# BPM_Mainboard.net
KiCad netlist of a schematic drawn in Altium Designer
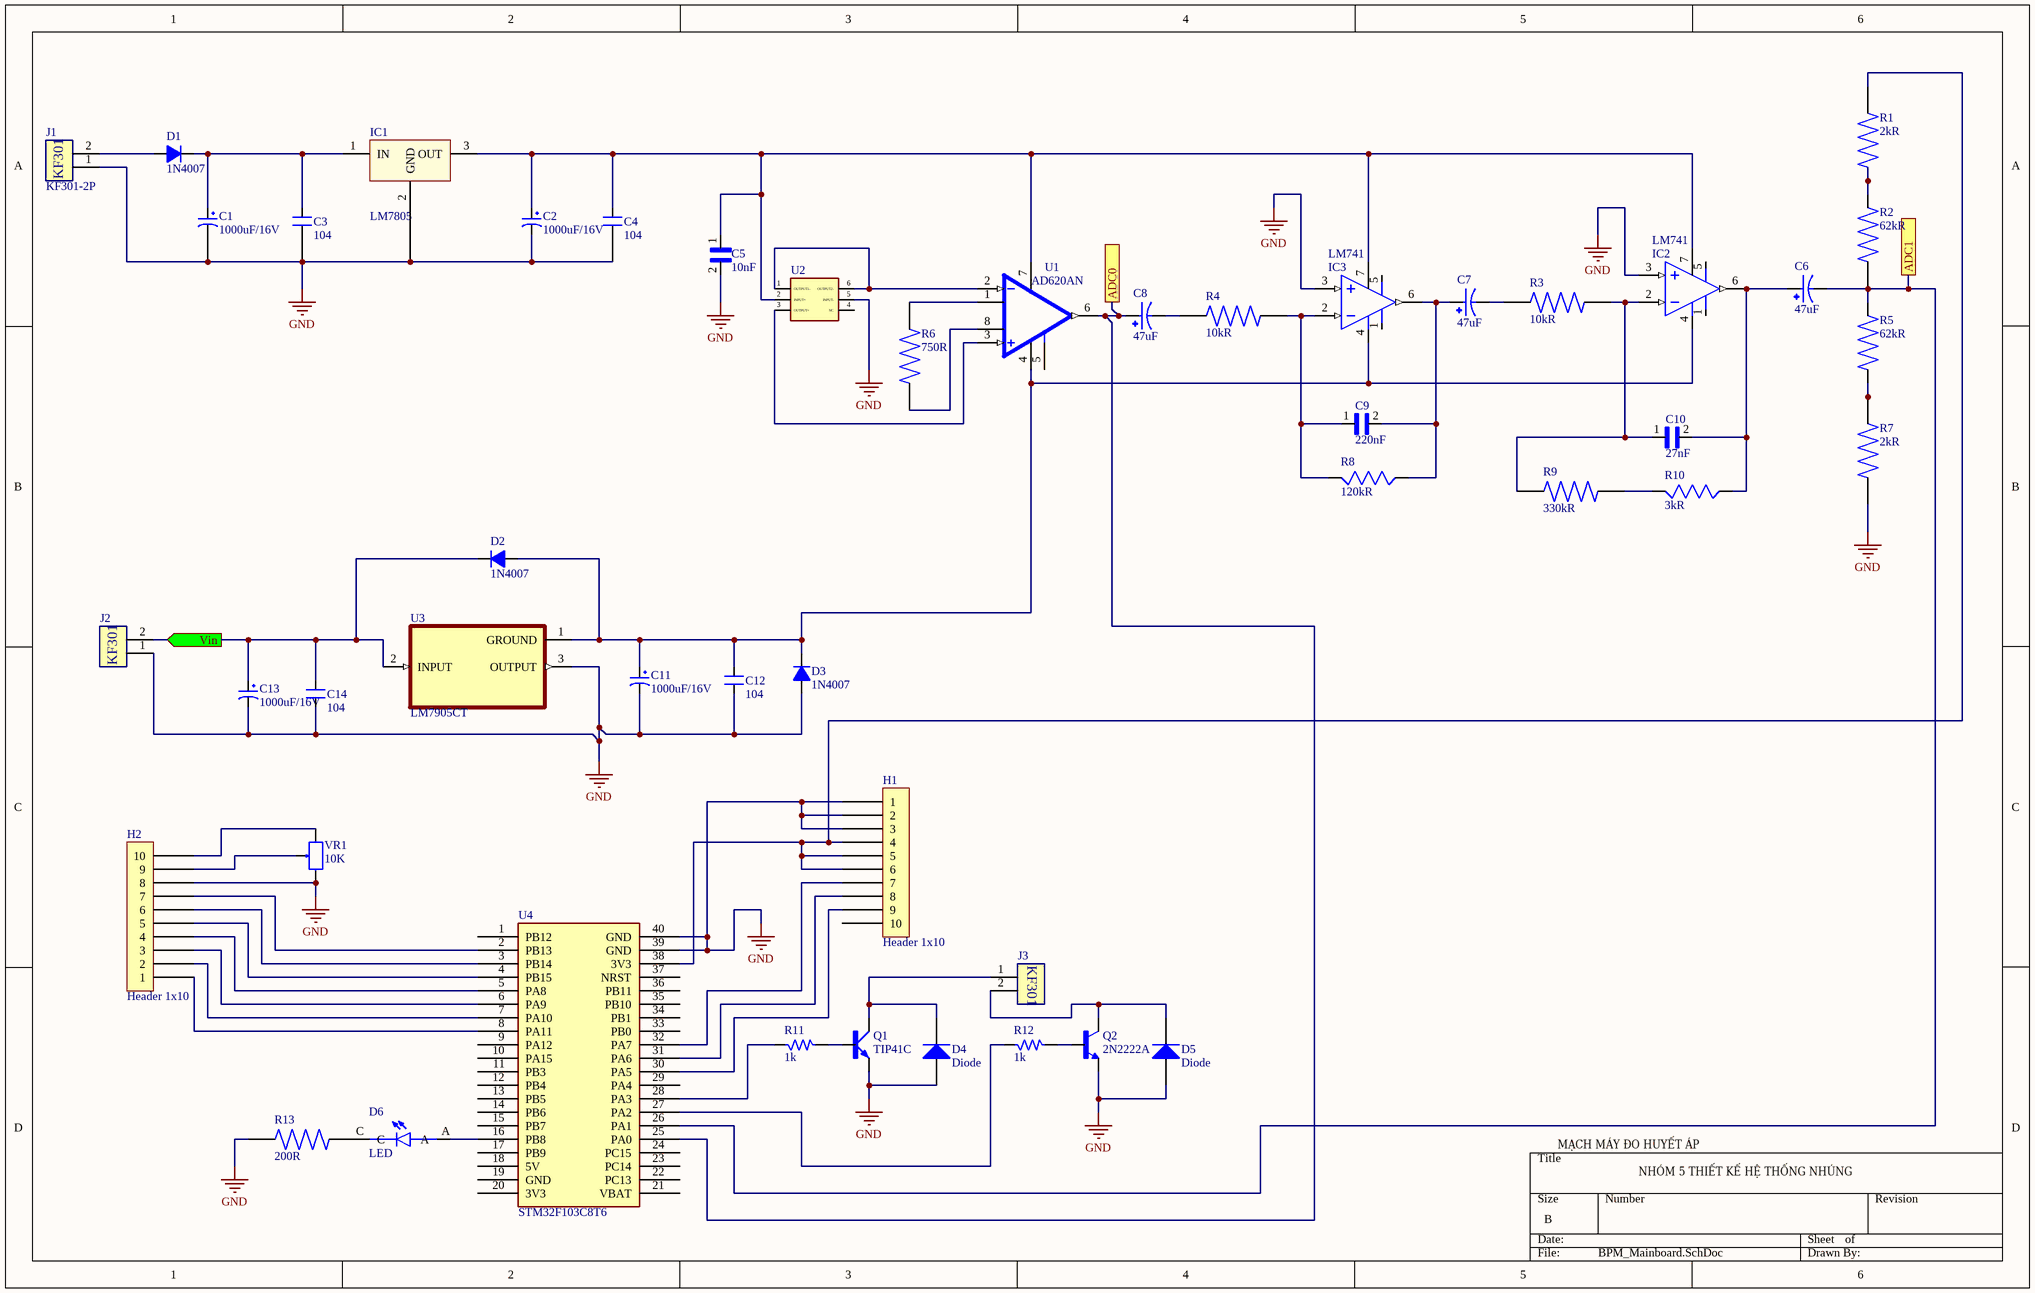
[diagram p0: BPM_Mainboard.SchDoc]

(export (version "E")
  (design (tool "Eeschema 10.0.6"))
  (components
    (comp (ref "C1")
      (value "1000uF/16V")
      (footprint "CP1.5/3.4")
      (description "Cap 1000uF/16V - 220uF/50V")
      (libsource (lib "syhaunguyen") (part "CP4"))
    )
    (comp (ref "C2")
      (value "1000uF/16V")
      (footprint "CP1.5/3.4")
      (description "Cap 1000uF/16V - 220uF/50V")
      (libsource (lib "syhaunguyen") (part "CP4"))
    )
    (comp (ref "C3")
      (value "104")
      (footprint "CN2")
      (description "Cap np 104 => 105pF")
      (libsource (lib "syhaunguyen") (part "CN2"))
    )
    (comp (ref "C4")
      (value "104")
      (footprint "CN2")
      (description "Cap np 104 => 105pF")
      (libsource (lib "syhaunguyen") (part "CN2"))
    )
    (comp (ref "C5")
      (value "10nF")
      (footprint "CAPC2012X145N")
      (description "0805 10nF 50 V Â±10 % Tolerance X7R SMT Multilayer Ceramic Chip Capacitor")
      (fields (field (name "MP") "VJ0805Y103KXAMC") (field (name "MF") "Vishay Vitramon"))
      (libsource (lib "VJ0805Y103KXAMC") (part "VJ0805Y103KXAMC"))
    )
    (comp (ref "C6")
      (value "47uF")
      (footprint "CAPPRD250W50D630H1120")
      (description "47ÂµF 50V Aluminum Electrolytic Capacitors Radial, Can 5000 Hrs @ 105Â°C")
      (fields (field (name "MF") "Panasonic") (field (name "MP") "EEUFR1H470"))
      (libsource (lib "EEUFR1H470") (part "EEUFR1H470"))
    )
    (comp (ref "C7")
      (value "47uF")
      (footprint "CAPPRD250W50D630H1120")
      (description "47ÂµF 50V Aluminum Electrolytic Capacitors Radial, Can 5000 Hrs @ 105Â°C")
      (fields (field (name "MF") "Panasonic") (field (name "MP") "EEUFR1H470"))
      (libsource (lib "EEUFR1H470") (part "EEUFR1H470"))
    )
    (comp (ref "C8")
      (value "47uF")
      (footprint "CAPPRD250W50D630H1120")
      (description "47ÂµF 50V Aluminum Electrolytic Capacitors Radial, Can 5000 Hrs @ 105Â°C")
      (fields (field (name "MF") "Panasonic") (field (name "MP") "EEUFR1H470"))
      (libsource (lib "EEUFR1H470") (part "EEUFR1H470"))
    )
    (comp (ref "C9")
      (value "220nF")
      (footprint "CAPC3216X94N")
      (description "Cap Ceramic 0.012uF 100V X7R 10% SMD 1206 125Â°C Paper T/R")
      (fields (field (name "MP") "12061C123KAT2A"))
      (libsource (lib "12061C123KAT2A") (part "12061C123KAT2A"))
    )
    (comp (ref "C10")
      (value "27nF")
      (footprint "CAPC2012X94N")
      (description "Cap Ceramic 0.027uF 50V X7R 10% SMD 0805 125Â°C Paper T/R")
      (fields (field (name "MP") "LD055C273KAB2A"))
      (libsource (lib "LD055C273KAB2A") (part "LD055C273KAB2A"))
    )
    (comp (ref "C11")
      (value "1000uF/16V")
      (footprint "CP1.5/3.4")
      (description "Cap 1000uF/16V - 220uF/50V")
      (libsource (lib "syhaunguyen") (part "CP4"))
    )
    (comp (ref "C12")
      (value "104")
      (footprint "CN2")
      (description "Cap np 104 => 105pF")
      (libsource (lib "syhaunguyen") (part "CN2"))
    )
    (comp (ref "C13")
      (value "1000uF/16V")
      (footprint "CP1.5/3.4")
      (description "Cap 1000uF/16V - 220uF/50V")
      (libsource (lib "syhaunguyen") (part "CP4"))
    )
    (comp (ref "C14")
      (value "104")
      (footprint "CN2")
      (description "Cap np 104 => 105pF")
      (libsource (lib "syhaunguyen") (part "CN2"))
    )
    (comp (ref "D1")
      (value "1N4007")
      (footprint "D1A")
      (description "Diode 1A")
      (libsource (lib "syhaunguyen") (part "D1A"))
    )
    (comp (ref "D2")
      (value "1N4007")
      (footprint "D1A")
      (description "Diode 1A")
      (libsource (lib "syhaunguyen") (part "D1A"))
    )
    (comp (ref "D3")
      (value "1N4007")
      (footprint "D1A")
      (description "Diode 1A")
      (libsource (lib "syhaunguyen") (part "D1A"))
    )
    (comp (ref "D4")
      (value "Diode")
      (footprint "DO-41")
      (description "1 Amp General Purpose Rectifier")
      (fields (field (name "PUBLISHER") "Altium Limited"))
      (libsource (lib "Miscellaneous Devices") (part "Diode 1N4007"))
    )
    (comp (ref "D5")
      (value "Diode")
      (footprint "DO-41")
      (description "1 Amp General Purpose Rectifier")
      (fields (field (name "PUBLISHER") "Altium Limited"))
      (libsource (lib "Miscellaneous Devices") (part "Diode 1N4007"))
    )
    (comp (ref "D6")
      (value "LED")
      (footprint "LEDC2012X120N")
      (description "LED RED DIFFUSED 0805 SMD")
      (fields (field (name "MP") "SML-LXT0805SRW-TR"))
      (libsource (lib "SML-LXT0805SRW-TR") (part "SML-LXT0805SRW-TR"))
    )
    (comp (ref "H1")
      (value "Header 1x10")
      (footprint "Header 1x10 male")
      (libsource (lib "") (part "Header 1x10_1"))
    )
    (comp (ref "H2")
      (value "Header 1x10")
      (footprint "Header 1x10 male")
      (libsource (lib "Headers") (part "Header 1x10"))
    )
    (comp (ref "IC1")
      (value "LM7805")
      (footprint "QTO-220")
      (description "On ap +, from + 5 to + 24VDC")
      (libsource (lib "syhaunguyen") (part "LM78xx"))
    )
    (comp (ref "IC2")
      (value "LM741")
      (footprint "DIP8/W0.3")
      (description "Single OA")
      (libsource (lib "syhaunguyen") (part "LM741"))
    )
    (comp (ref "IC3")
      (value "LM741")
      (footprint "DIP8/W0.3")
      (description "Single OA")
      (libsource (lib "syhaunguyen") (part "LM741"))
    )
    (comp (ref "J1")
      (value "KF301-2P")
      (footprint "KF301-5.0-2P")
      (libsource (lib "KF301") (part "KF301-2P"))
    )
    (comp (ref "J2")
      (value "~")
      (footprint "KF301-5.0-2P")
      (libsource (lib "KF301") (part "Terminal_block1"))
    )
    (comp (ref "J3") (value "~") (footprint "KF301-5.0-2P") (libsource (lib "") (part "Terminal_block1_1")))
    (comp (ref "Q1")
      (value "TIP41C")
      (footprint "TO220AV")
      (description "Bipolar _BJT_ Transistor NPN 100V 6A 3MHz 2W Through Hole TO-220-3")
      (fields (field (name "MF") "Central Semiconductor"))
      (libsource (lib "TIP41C") (part "TIP41C"))
    )
    (comp (ref "Q2")
      (value "2N2222A")
      (footprint "TO92254P470H750-3")
      (description "Bipolar (BJT) Transistor NPN 40 V 600 mA 250MHz 625 mW Through Hole TO-92")
      (fields (field (name "MF") "Diotec Semiconductor"))
      (libsource (lib "2N2222A") (part "2N2222A"))
    )
    (comp (ref "R1")
      (value "2kR")
      (footprint "RESC2012X60N")
      (fields (field (name "MP") "CR0805-JW-202ELF"))
      (libsource (lib "CR0805-JW-202ELF") (part "CR0805-JW-202ELF"))
    )
    (comp (ref "R2")
      (value "62kR")
      (footprint "RESC2012X60N")
      (description "Resistor: thick film; SMD; 0805; 62kÎ©; 0.125W; Â±5%; -55Ã·155Â°C")
      (fields (field (name "MP") "RC0805JR-0762KL"))
      (libsource (lib "RC0805JR-0762KL") (part "RC0805JR-0762KL"))
    )
    (comp (ref "R3")
      (value "10kR")
      (footprint "RESC2012X65N")
      (fields
        (field (name "MF") "{'manufacturer': u'Stackpole Electronics Inc'}")
        (field (name "MP") "RMCF0805FT10K0")
      )
      (libsource (lib "RMCF0805FT10K0") (part "RMCF0805FT10K0"))
    )
    (comp (ref "R4")
      (value "10kR")
      (footprint "RESC2012X65N")
      (fields
        (field (name "MF") "{'manufacturer': u'Stackpole Electronics Inc'}")
        (field (name "MP") "RMCF0805FT10K0")
      )
      (libsource (lib "RMCF0805FT10K0") (part "RMCF0805FT10K0"))
    )
    (comp (ref "R5")
      (value "62kR")
      (footprint "RESC2012X60N")
      (description "Resistor: thick film; SMD; 0805; 62kÎ©; 0.125W; Â±5%; -55Ã·155Â°C")
      (fields (field (name "MP") "RC0805JR-0762KL"))
      (libsource (lib "RC0805JR-0762KL") (part "RC0805JR-0762KL"))
    )
    (comp (ref "R6")
      (value "750R")
      (footprint "RESC2012X60N")
      (fields (field (name "MP") "AF0805JR-07750RL"))
      (libsource (lib "AF0805JR-07750RL") (part "AF0805JR-07750RL"))
    )
    (comp (ref "R7")
      (value "2kR")
      (footprint "RESC2012X60N")
      (fields (field (name "MP") "CR0805-JW-202ELF"))
      (libsource (lib "CR0805-JW-202ELF") (part "CR0805-JW-202ELF"))
    )
    (comp (ref "R8")
      (value "120kR")
      (footprint "RESC2012X60N")
      (fields (field (name "MP") "RC0805FR-13120KL"))
      (libsource (lib "RC0805FR-13120KL") (part "RC0805FR-13120KL"))
    )
    (comp (ref "R9")
      (value "330kR")
      (footprint "RESC2012X65N")
      (fields (field (name "MP") "SFR10EZPF3303"))
      (libsource (lib "SFR10EZPF3303") (part "SFR10EZPF3303"))
    )
    (comp (ref "R10")
      (value "3kR")
      (footprint "RESC2012X60N")
      (fields (field (name "MF") "{'manufacturer': u'YAGEO'}") (field (name "MP") "RC0805FR-133KL"))
      (libsource (lib "RC0805FR-133KL") (part "RC0805FR-133KL"))
    )
    (comp (ref "R11")
      (value "1k")
      (footprint "SM-1206")
      (description "Resistor 1/4W")
      (libsource (lib "syhaunguyen") (part "R"))
    )
    (comp (ref "R12")
      (value "1k")
      (footprint "SM-1206")
      (description "Resistor 1/4W")
      (libsource (lib "syhaunguyen") (part "R"))
    )
    (comp (ref "R13")
      (value "200R")
      (footprint "RESC2012X65N")
      (fields (field (name "MP") "MCR10EZPJ201"))
      (libsource (lib "MCR10EZPJ201") (part "MCR10EZPJ201"))
    )
    (comp (ref "U1")
      (value "AD620AN")
      (footprint "DIP787W46P254L1016H533Q8")
      (description "Instrumentation Amplifier 1 Circuit - 8-PDIP")
      (fields (field (name "MF") "Analog Devices"))
      (libsource (lib "AD620AN") (part "AD620AN"))
    )
    (comp (ref "U2")
      (value "~")
      (footprint "MPS20N0200D_Foot")
      (description "Pressure Sensor")
      (libsource (lib "MPS20N0040D-S") (part "MPS20N0200D"))
    )
    (comp (ref "U3")
      (value "LM7905CT")
      (footprint "TO254P1054X470X1955-3")
      (description "Linear Voltage Regulator IC 1 Output 1A TO-220-3")
      (fields (field (name "MF") "ON Semiconductor"))
      (libsource (lib "LM7905CT") (part "LM7905CT"))
    )
    (comp (ref "U4")
      (value "STM32F103C8T6")
      (footprint "Stm32 BluePill")
      (description "Designed By @Alixahedi")
      (libsource (lib "Stm32 Blue Pill") (part "BluePill"))
    )
    (comp (ref "VR1")
      (value "10K")
      (footprint "VOL_1")
      (description "Var Resistor")
      (libsource (lib "Cty1") (part "Var Resitor"))
    )
  )
  (nets
    (net (code "1") (name "/ADC0") (class "Default")
      (node (ref "C8") (pin "P") (pinfunction "P_P") (pintype "passive"))
      (node (ref "U1") (pin "6") (pinfunction "OUTPUT_6") (pintype "output"))
      (node (ref "U4") (pin "25") (pinfunction "PA0_25") (pintype "passive"))
    )
    (net (code "2") (name "/ADC1") (class "Default")
      (node (ref "C6") (pin "N") (pinfunction "N_N") (pintype "passive"))
      (node (ref "R2") (pin "1") (pinfunction "1_1") (pintype "passive"))
      (node (ref "R5") (pin "2") (pinfunction "2_2") (pintype "passive"))
      (node (ref "U4") (pin "26") (pinfunction "PA1_26") (pintype "passive"))
    )
    (net (code "3") (name "/Vin") (class "Default")
      (node (ref "C13") (pin "1") (pinfunction "1_1") (pintype "passive"))
      (node (ref "C14") (pin "1") (pinfunction "1_1") (pintype "passive"))
      (node (ref "D2") (pin "2") (pinfunction "K_2") (pintype "passive"))
      (node (ref "J2") (pin "2") (pinfunction "2_2") (pintype "passive"))
      (node (ref "U3") (pin "2") (pinfunction "INPUT_2") (pintype "input"))
    )
    (net (code "4") (name "GND") (class "Default")
      (node (ref "C1") (pin "2") (pinfunction "2_2") (pintype "passive"))
      (node (ref "C11") (pin "2") (pinfunction "2_2") (pintype "passive"))
      (node (ref "C12") (pin "2") (pinfunction "2_2") (pintype "passive"))
      (node (ref "C13") (pin "2") (pinfunction "2_2") (pintype "passive"))
      (node (ref "C14") (pin "2") (pinfunction "2_2") (pintype "passive"))
      (node (ref "C2") (pin "2") (pinfunction "2_2") (pintype "passive"))
      (node (ref "C3") (pin "2") (pinfunction "2_2") (pintype "passive"))
      (node (ref "C4") (pin "2") (pinfunction "2_2") (pintype "passive"))
      (node (ref "C5") (pin "2") (pinfunction "2_2") (pintype "passive"))
      (node (ref "D3") (pin "1") (pinfunction "A_1") (pintype "passive"))
      (node (ref "D4") (pin "1") (pinfunction "A_1") (pintype "passive"))
      (node (ref "D5") (pin "1") (pinfunction "A_1") (pintype "passive"))
      (node (ref "H1") (pin "1") (pinfunction "1_1") (pintype "passive"))
      (node (ref "H1") (pin "2") (pinfunction "2_2") (pintype "passive"))
      (node (ref "H1") (pin "3") (pinfunction "3_3") (pintype "passive"))
      (node (ref "H2") (pin "8") (pinfunction "8_8") (pintype "passive"))
      (node (ref "IC1") (pin "2") (pinfunction "GND_2") (pintype "passive"))
      (node (ref "IC2") (pin "3") (pinfunction "IN+_3") (pintype "input"))
      (node (ref "IC3") (pin "3") (pinfunction "IN+_3") (pintype "input"))
      (node (ref "J1") (pin "1") (pinfunction "1_1") (pintype "passive"))
      (node (ref "J2") (pin "1") (pinfunction "1_1") (pintype "passive"))
      (node (ref "Q1") (pin "E") (pinfunction "E_E") (pintype "passive"))
      (node (ref "Q2") (pin "1") (pinfunction "E_1") (pintype "passive"))
      (node (ref "R13") (pin "1") (pinfunction "1_1") (pintype "passive"))
      (node (ref "R7") (pin "2") (pinfunction "2_2") (pintype "passive"))
      (node (ref "U2") (pin "5") (pinfunction "INPUT-_5") (pintype "passive"))
      (node (ref "U3") (pin "3") (pinfunction "OUTPUT_3") (pintype "output"))
      (node (ref "U4") (pin "39") (pinfunction "GND_39") (pintype "passive"))
      (node (ref "U4") (pin "40") (pinfunction "GND_40") (pintype "passive"))
      (node (ref "VR1") (pin "1") (pinfunction "1_1") (pintype "passive"))
    )
    (net (code "5") (name "Net-(C7-PadN)") (class "Default")
      (node (ref "C7") (pin "N") (pinfunction "N_N") (pintype "passive"))
      (node (ref "R3") (pin "1") (pinfunction "1_1") (pintype "passive"))
    )
    (net (code "6") (name "Net-(C8-PadN)") (class "Default")
      (node (ref "C8") (pin "N") (pinfunction "N_N") (pintype "passive"))
      (node (ref "R4") (pin "1") (pinfunction "1_1") (pintype "passive"))
    )
    (net (code "7") (name "Net-(D1-A)") (class "Default")
      (node (ref "D1") (pin "1") (pinfunction "A_1") (pintype "passive"))
      (node (ref "J1") (pin "2") (pinfunction "2_2") (pintype "passive"))
    )
    (net (code "8") (name "Net-(D1-K)") (class "Default")
      (node (ref "C1") (pin "1") (pinfunction "1_1") (pintype "passive"))
      (node (ref "C3") (pin "1") (pinfunction "1_1") (pintype "passive"))
      (node (ref "D1") (pin "2") (pinfunction "K_2") (pintype "passive"))
      (node (ref "IC1") (pin "1") (pinfunction "IN_1") (pintype "passive"))
    )
    (net (code "9") (name "Net-(D2-A)") (class "Default")
      (node (ref "C11") (pin "1") (pinfunction "1_1") (pintype "passive"))
      (node (ref "C12") (pin "1") (pinfunction "1_1") (pintype "passive"))
      (node (ref "D2") (pin "1") (pinfunction "A_1") (pintype "passive"))
      (node (ref "D3") (pin "2") (pinfunction "K_2") (pintype "passive"))
      (node (ref "IC2") (pin "4") (pinfunction "-V_4") (pintype "passive"))
      (node (ref "IC3") (pin "4") (pinfunction "-V_4") (pintype "passive"))
      (node (ref "U1") (pin "4") (pinfunction "-VS_4") (pintype "power_in"))
      (node (ref "U3") (pin "1") (pinfunction "GROUND_1") (pintype "power_in"))
    )
    (net (code "10") (name "Net-(D4-K)") (class "Default")
      (node (ref "D4") (pin "2") (pinfunction "K_2") (pintype "passive"))
      (node (ref "J3") (pin "1") (pinfunction "1_1") (pintype "passive"))
      (node (ref "Q1") (pin "C") (pinfunction "C_C") (pintype "passive"))
    )
    (net (code "11") (name "Net-(D5-K)") (class "Default")
      (node (ref "D5") (pin "2") (pinfunction "K_2") (pintype "passive"))
      (node (ref "J3") (pin "2") (pinfunction "2_2") (pintype "passive"))
      (node (ref "Q2") (pin "3") (pinfunction "C_3") (pintype "passive"))
    )
    (net (code "12") (name "Net-(D6-PadC)") (class "Default")
      (node (ref "D6") (pin "C") (pinfunction "C_C") (pintype "passive"))
      (node (ref "R13") (pin "2") (pinfunction "2_2") (pintype "passive"))
    )
    (net (code "13") (name "Net-(H1-Pad4)") (class "Default")
      (node (ref "H1") (pin "4") (pinfunction "4_4") (pintype "passive"))
      (node (ref "H1") (pin "5") (pinfunction "5_5") (pintype "passive"))
      (node (ref "H1") (pin "6") (pinfunction "6_6") (pintype "passive"))
      (node (ref "R1") (pin "1") (pinfunction "1_1") (pintype "passive"))
      (node (ref "U4") (pin "38") (pinfunction "3V3_38") (pintype "passive"))
    )
    (net (code "14") (name "Net-(H2-Pad9)") (class "Default")
      (node (ref "H2") (pin "9") (pinfunction "9_9") (pintype "passive"))
      (node (ref "VR1") (pin "2") (pinfunction "2_2") (pintype "passive"))
    )
    (net (code "15") (name "Net-(H2-Pad10)") (class "Default")
      (node (ref "H2") (pin "10") (pinfunction "10_10") (pintype "passive"))
      (node (ref "VR1") (pin "3") (pinfunction "3_3") (pintype "passive"))
    )
    (net (code "16") (name "Net-(IC1-OUT)") (class "Default")
      (node (ref "C2") (pin "1") (pinfunction "1_1") (pintype "passive"))
      (node (ref "C4") (pin "1") (pinfunction "1_1") (pintype "passive"))
      (node (ref "C5") (pin "1") (pinfunction "1_1") (pintype "passive"))
      (node (ref "IC1") (pin "3") (pinfunction "OUT_3") (pintype "passive"))
      (node (ref "IC2") (pin "7") (pinfunction "+V_7") (pintype "passive"))
      (node (ref "IC3") (pin "7") (pinfunction "+V_7") (pintype "passive"))
      (node (ref "U1") (pin "7") (pinfunction "+VS_7") (pintype "power_in"))
      (node (ref "U2") (pin "2") (pinfunction "INPUT+_2") (pintype "passive"))
    )
    (net (code "17") (name "Net-(IC2-IN-)") (class "Default")
      (node (ref "C10") (pin "1") (pinfunction "1_1") (pintype "passive"))
      (node (ref "IC2") (pin "2") (pinfunction "IN-_2") (pintype "input"))
      (node (ref "R3") (pin "2") (pinfunction "2_2") (pintype "passive"))
      (node (ref "R9") (pin "1") (pinfunction "1_1") (pintype "passive"))
    )
    (net (code "18") (name "Net-(IC2-OUT)") (class "Default")
      (node (ref "C10") (pin "2") (pinfunction "2_2") (pintype "passive"))
      (node (ref "C6") (pin "P") (pinfunction "P_P") (pintype "passive"))
      (node (ref "IC2") (pin "6") (pinfunction "OUT_6") (pintype "output"))
      (node (ref "R10") (pin "2") (pinfunction "2_2") (pintype "passive"))
    )
    (net (code "19") (name "Net-(IC3-IN-)") (class "Default")
      (node (ref "C9") (pin "1") (pinfunction "1_1") (pintype "passive"))
      (node (ref "IC3") (pin "2") (pinfunction "IN-_2") (pintype "input"))
      (node (ref "R4") (pin "2") (pinfunction "2_2") (pintype "passive"))
      (node (ref "R8") (pin "1") (pinfunction "1_1") (pintype "passive"))
    )
    (net (code "20") (name "Net-(IC3-OUT)") (class "Default")
      (node (ref "C7") (pin "P") (pinfunction "P_P") (pintype "passive"))
      (node (ref "C9") (pin "2") (pinfunction "2_2") (pintype "passive"))
      (node (ref "IC3") (pin "6") (pinfunction "OUT_6") (pintype "output"))
      (node (ref "R8") (pin "2") (pinfunction "2_2") (pintype "passive"))
    )
    (net (code "21") (name "Net-(Q1-PadB)") (class "Default")
      (node (ref "Q1") (pin "B") (pinfunction "B_B") (pintype "passive"))
      (node (ref "R11") (pin "2") (pinfunction "2_2") (pintype "passive"))
    )
    (net (code "22") (name "Net-(Q2-B)") (class "Default")
      (node (ref "Q2") (pin "2") (pinfunction "B_2") (pintype "passive"))
      (node (ref "R12") (pin "2") (pinfunction "2_2") (pintype "passive"))
    )
    (net (code "23") (name "Net-(R1-Pad2)") (class "Default")
      (node (ref "R1") (pin "2") (pinfunction "2_2") (pintype "passive"))
      (node (ref "R2") (pin "2") (pinfunction "2_2") (pintype "passive"))
    )
    (net (code "24") (name "Net-(R5-Pad1)") (class "Default")
      (node (ref "R5") (pin "1") (pinfunction "1_1") (pintype "passive"))
      (node (ref "R7") (pin "1") (pinfunction "1_1") (pintype "passive"))
    )
    (net (code "25") (name "Net-(R10-Pad1)") (class "Default")
      (node (ref "R10") (pin "1") (pinfunction "1_1") (pintype "passive"))
      (node (ref "R9") (pin "2") (pinfunction "2_2") (pintype "passive"))
    )
    (net (code "26") (name "Net-(U1-+IN)") (class "Default")
      (node (ref "U1") (pin "3") (pinfunction "+IN_3") (pintype "input"))
      (node (ref "U2") (pin "3") (pinfunction "OUTPUT+_3") (pintype "passive"))
    )
    (net (code "27") (name "Net-(U1--IN)") (class "Default")
      (node (ref "U1") (pin "2") (pinfunction "-IN_2") (pintype "input"))
      (node (ref "U2") (pin "1") (pinfunction "OUTPUT1-_1") (pintype "passive"))
      (node (ref "U2") (pin "6") (pinfunction "OUTPUT2-_6") (pintype "passive"))
    )
    (net (code "28") (name "Net-(U1-RG_1)") (class "Default")
      (node (ref "R6") (pin "2") (pinfunction "2_2") (pintype "passive"))
      (node (ref "U1") (pin "1") (pinfunction "RG_1_1") (pintype "passive"))
    )
    (net (code "29") (name "Net-(U1-RG_8)") (class "Default")
      (node (ref "R6") (pin "1") (pinfunction "1_1") (pintype "passive"))
      (node (ref "U1") (pin "8") (pinfunction "RG_8_8") (pintype "passive"))
    )
    (net (code "30") (name "Net-(U4-PA2)") (class "Default")
      (node (ref "R12") (pin "1") (pinfunction "1_1") (pintype "passive"))
      (node (ref "U4") (pin "27") (pinfunction "PA2_27") (pintype "passive"))
    )
    (net (code "31") (name "Net-(U4-PA3)") (class "Default")
      (node (ref "R11") (pin "1") (pinfunction "1_1") (pintype "passive"))
      (node (ref "U4") (pin "28") (pinfunction "PA3_28") (pintype "passive"))
    )
    (net (code "32") (name "Net-(U4-PA5)") (class "Default")
      (node (ref "H1") (pin "9") (pinfunction "9_9") (pintype "passive"))
      (node (ref "U4") (pin "30") (pinfunction "PA5_30") (pintype "passive"))
    )
    (net (code "33") (name "Net-(U4-PA6)") (class "Default")
      (node (ref "H1") (pin "8") (pinfunction "8_8") (pintype "passive"))
      (node (ref "U4") (pin "31") (pinfunction "PA6_31") (pintype "passive"))
    )
    (net (code "34") (name "Net-(U4-PA7)") (class "Default")
      (node (ref "H1") (pin "7") (pinfunction "7_7") (pintype "passive"))
      (node (ref "U4") (pin "32") (pinfunction "PA7_32") (pintype "passive"))
    )
    (net (code "35") (name "Net-(U4-PA8)") (class "Default")
      (node (ref "H2") (pin "4") (pinfunction "4_4") (pintype "passive"))
      (node (ref "U4") (pin "5") (pinfunction "PA8_5") (pintype "passive"))
    )
    (net (code "36") (name "Net-(U4-PA9)") (class "Default")
      (node (ref "H2") (pin "3") (pinfunction "3_3") (pintype "passive"))
      (node (ref "U4") (pin "6") (pinfunction "PA9_6") (pintype "passive"))
    )
    (net (code "37") (name "Net-(U4-PA10)") (class "Default")
      (node (ref "H2") (pin "2") (pinfunction "2_2") (pintype "passive"))
      (node (ref "U4") (pin "7") (pinfunction "PA10_7") (pintype "passive"))
    )
    (net (code "38") (name "Net-(U4-PA11)") (class "Default")
      (node (ref "H2") (pin "1") (pinfunction "1_1") (pintype "passive"))
      (node (ref "U4") (pin "8") (pinfunction "PA11_8") (pintype "passive"))
    )
    (net (code "39") (name "Net-(U4-PB8)") (class "Default")
      (node (ref "D6") (pin "A") (pinfunction "A_A") (pintype "passive"))
      (node (ref "U4") (pin "16") (pinfunction "PB8_16") (pintype "passive"))
    )
    (net (code "40") (name "Net-(U4-PB13)") (class "Default")
      (node (ref "H2") (pin "7") (pinfunction "7_7") (pintype "passive"))
      (node (ref "U4") (pin "2") (pinfunction "PB13_2") (pintype "passive"))
    )
    (net (code "41") (name "Net-(U4-PB14)") (class "Default")
      (node (ref "H2") (pin "6") (pinfunction "6_6") (pintype "passive"))
      (node (ref "U4") (pin "3") (pinfunction "PB14_3") (pintype "passive"))
    )
    (net (code "42") (name "Net-(U4-PB15)") (class "Default")
      (node (ref "H2") (pin "5") (pinfunction "5_5") (pintype "passive"))
      (node (ref "U4") (pin "4") (pinfunction "PB15_4") (pintype "passive"))
    )
    (net (code "43") (name "unconnected-(H1-Pad10)") (class "Default")
      (node (ref "H1") (pin "10") (pinfunction "10_10") (pintype "passive"))
    )
    (net (code "44") (name "unconnected-(IC2-Vos-Pad1)") (class "Default")
      (node (ref "IC2") (pin "1") (pinfunction "Vos_1") (pintype "passive"))
    )
    (net (code "45") (name "unconnected-(IC2-Vos-Pad5)") (class "Default")
      (node (ref "IC2") (pin "5") (pinfunction "Vos_5") (pintype "passive"))
    )
    (net (code "46") (name "unconnected-(IC3-Vos-Pad1)") (class "Default")
      (node (ref "IC3") (pin "1") (pinfunction "Vos_1") (pintype "passive"))
    )
    (net (code "47") (name "unconnected-(IC3-Vos-Pad5)") (class "Default")
      (node (ref "IC3") (pin "5") (pinfunction "Vos_5") (pintype "passive"))
    )
    (net (code "48") (name "unconnected-(U1-REF-Pad5)") (class "Default")
      (node (ref "U1") (pin "5") (pinfunction "REF_5") (pintype "power_in"))
    )
    (net (code "49") (name "unconnected-(U2-NC-Pad4)") (class "Default")
      (node (ref "U2") (pin "4") (pinfunction "NC_4") (pintype "passive"))
    )
    (net (code "50") (name "unconnected-(U4-3V3-Pad20)") (class "Default")
      (node (ref "U4") (pin "20") (pinfunction "3V3_20") (pintype "passive"))
    )
    (net (code "51") (name "unconnected-(U4-5V-Pad18)") (class "Default")
      (node (ref "U4") (pin "18") (pinfunction "5V_18") (pintype "passive"))
    )
    (net (code "52") (name "unconnected-(U4-GND-Pad19)") (class "Default")
      (node (ref "U4") (pin "19") (pinfunction "GND_19") (pintype "passive"))
    )
    (net (code "53") (name "unconnected-(U4-NRST-Pad37)") (class "Default")
      (node (ref "U4") (pin "37") (pinfunction "NRST_37") (pintype "passive"))
    )
    (net (code "54") (name "unconnected-(U4-PA4-Pad29)") (class "Default")
      (node (ref "U4") (pin "29") (pinfunction "PA4_29") (pintype "passive"))
    )
    (net (code "55") (name "unconnected-(U4-PA12-Pad9)") (class "Default")
      (node (ref "U4") (pin "9") (pinfunction "PA12_9") (pintype "passive"))
    )
    (net (code "56") (name "unconnected-(U4-PA15-Pad10)") (class "Default")
      (node (ref "U4") (pin "10") (pinfunction "PA15_10") (pintype "passive"))
    )
    (net (code "57") (name "unconnected-(U4-PB0-Pad33)") (class "Default")
      (node (ref "U4") (pin "33") (pinfunction "PB0_33") (pintype "passive"))
    )
    (net (code "58") (name "unconnected-(U4-PB1-Pad34)") (class "Default")
      (node (ref "U4") (pin "34") (pinfunction "PB1_34") (pintype "passive"))
    )
    (net (code "59") (name "unconnected-(U4-PB3-Pad11)") (class "Default")
      (node (ref "U4") (pin "11") (pinfunction "PB3_11") (pintype "passive"))
    )
    (net (code "60") (name "unconnected-(U4-PB4-Pad12)") (class "Default")
      (node (ref "U4") (pin "12") (pinfunction "PB4_12") (pintype "passive"))
    )
    (net (code "61") (name "unconnected-(U4-PB5-Pad13)") (class "Default")
      (node (ref "U4") (pin "13") (pinfunction "PB5_13") (pintype "passive"))
    )
    (net (code "62") (name "unconnected-(U4-PB6-Pad14)") (class "Default")
      (node (ref "U4") (pin "14") (pinfunction "PB6_14") (pintype "passive"))
    )
    (net (code "63") (name "unconnected-(U4-PB7-Pad15)") (class "Default")
      (node (ref "U4") (pin "15") (pinfunction "PB7_15") (pintype "passive"))
    )
    (net (code "64") (name "unconnected-(U4-PB9-Pad17)") (class "Default")
      (node (ref "U4") (pin "17") (pinfunction "PB9_17") (pintype "passive"))
    )
    (net (code "65") (name "unconnected-(U4-PB10-Pad35)") (class "Default")
      (node (ref "U4") (pin "35") (pinfunction "PB10_35") (pintype "passive"))
    )
    (net (code "66") (name "unconnected-(U4-PB11-Pad36)") (class "Default")
      (node (ref "U4") (pin "36") (pinfunction "PB11_36") (pintype "passive"))
    )
    (net (code "67") (name "unconnected-(U4-PB12-Pad1)") (class "Default")
      (node (ref "U4") (pin "1") (pinfunction "PB12_1") (pintype "passive"))
    )
    (net (code "68") (name "unconnected-(U4-PC13-Pad22)") (class "Default")
      (node (ref "U4") (pin "22") (pinfunction "PC13_22") (pintype "passive"))
    )
    (net (code "69") (name "unconnected-(U4-PC14-Pad23)") (class "Default")
      (node (ref "U4") (pin "23") (pinfunction "PC14_23") (pintype "passive"))
    )
    (net (code "70") (name "unconnected-(U4-PC15-Pad24)") (class "Default")
      (node (ref "U4") (pin "24") (pinfunction "PC15_24") (pintype "passive"))
    )
    (net (code "71") (name "unconnected-(U4-VBAT-Pad21)") (class "Default")
      (node (ref "U4") (pin "21") (pinfunction "VBAT_21") (pintype "passive"))
    )
  )
)
